# 06_POWER.net
KiCad netlist of a schematic drawn in Altium Designer
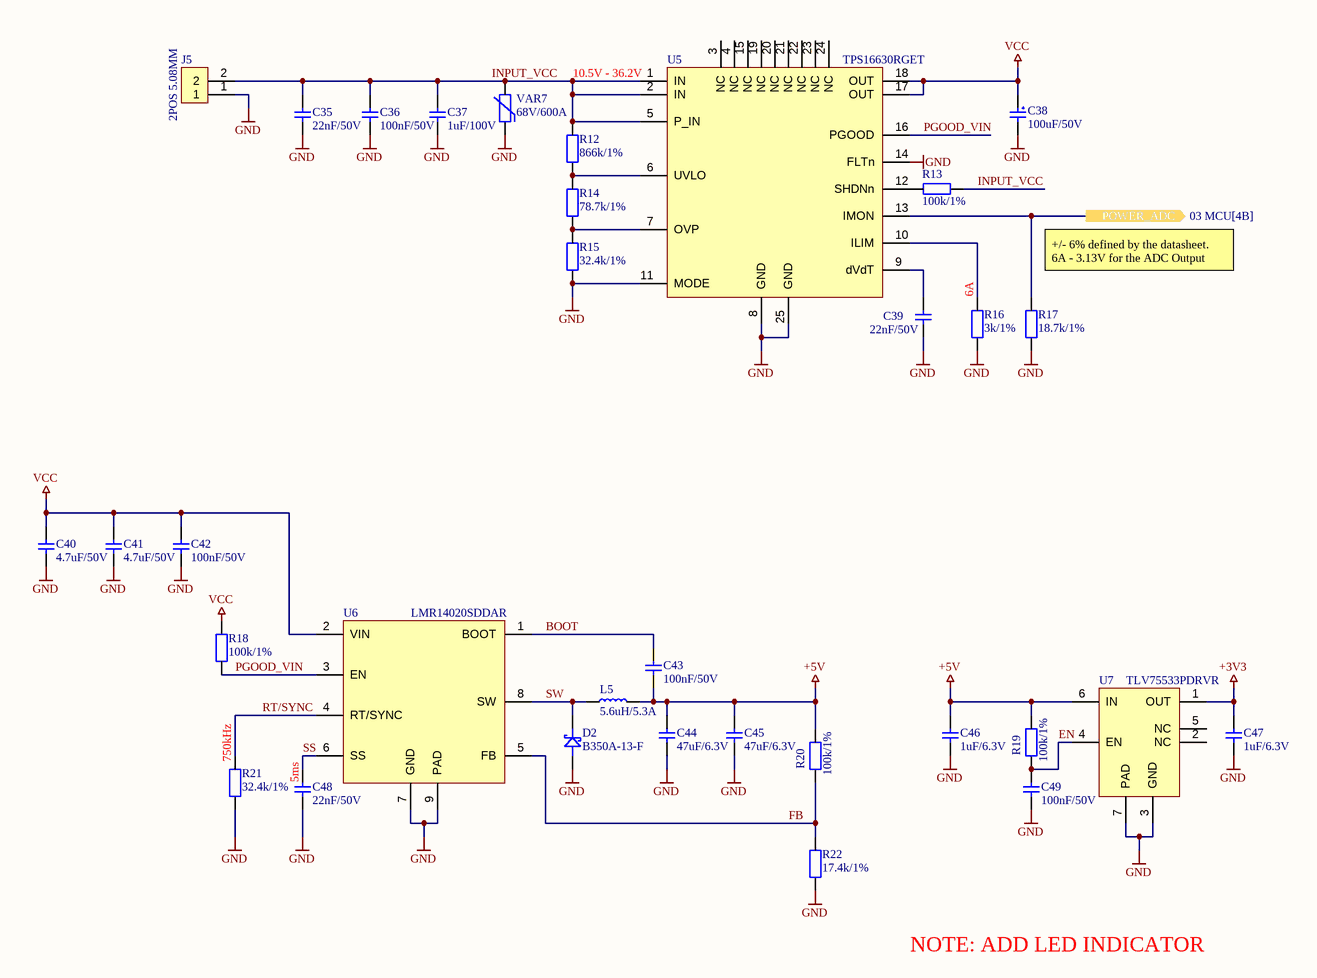
[diagram p0: 06 POWER.SchDoc]

(export (version "E")
  (design (tool "Eeschema 10.0.6"))
  (components
    (comp (ref "C35")
      (value "22nF/50V")
      (footprint "CAPC1005X06M-0402")
      (description "0.022 µF ±10% 50V Ceramic Capacitor X7R 0402 (1005 Metric)")
      (fields (field (name "MPN") "GRM155R71H223KA12D"))
      (libsource (lib "Symbol") (part "GRM155R71H223KA12D"))
    )
    (comp (ref "C36")
      (value "100nF/50V")
      (footprint "CAPC1005X06M-0402")
      (description "0.1 µF ±10% 50V Ceramic Capacitor X7R 0402 (1005 Metric)")
      (fields (field (name "MPN") "GRM155R71H104KE14D"))
      (libsource (lib "Symbol") (part "GRM155R71H104KE14D"))
    )
    (comp (ref "C37")
      (value "1uF/100V")
      (footprint "CAPC2012X14M")
      (description "1 µF ±10% 100V Ceramic Capacitor X7S 0805 (2012 Metric)")
      (fields (field (name "MPN") "GRM21BC72A105KE01L"))
      (libsource (lib "Symbol") (part "GRM21BC72A105KE01L"))
    )
    (comp (ref "C38")
      (value "100uF/50V")
      (footprint "A768KS107M1HLAE030")
      (description "100 µF 50 V Aluminum - Polymer Capacitors Radial, Can - SMD 30mOhm 2000 Hrs @ 125°C")
      (fields (field (name "MPN") "A768KS107M1HLAE030"))
      (libsource (lib "Symbol") (part "A768KS107M1HLAE030"))
    )
    (comp (ref "C39")
      (value "22nF/50V")
      (footprint "CAPC1005X06M-0402")
      (description "0.022 µF ±10% 50V Ceramic Capacitor X7R 0402 (1005 Metric)")
      (fields (field (name "MPN") "GRM155R71H223KA12D"))
      (libsource (lib "Symbol") (part "GRM155R71H223KA12D"))
    )
    (comp (ref "C40")
      (value "4.7uF/50V")
      (footprint "CAPC2012X14M")
      (description "4.7 µF ±10% 50V Ceramic Capacitor X5R 0805 (2012 Metric)")
      (fields (field (name "MPN") "GRM21BR61H475KE51L"))
      (libsource (lib "Symbol") (part "GRM21BR61H475KE51L"))
    )
    (comp (ref "C41")
      (value "4.7uF/50V")
      (footprint "CAPC2012X14M")
      (description "4.7 µF ±10% 50V Ceramic Capacitor X5R 0805 (2012 Metric)")
      (fields (field (name "MPN") "GRM21BR61H475KE51L"))
      (libsource (lib "Symbol") (part "GRM21BR61H475KE51L"))
    )
    (comp (ref "C42")
      (value "100nF/50V")
      (footprint "CAPC1005X06M-0402")
      (description "0.1 µF ±10% 50V Ceramic Capacitor X7R 0402 (1005 Metric)")
      (fields (field (name "MPN") "GRM155R71H104KE14D"))
      (libsource (lib "Symbol") (part "GRM155R71H104KE14D"))
    )
    (comp (ref "C43")
      (value "100nF/50V")
      (footprint "CAPC1005X06M-0402")
      (description "0.1 µF ±10% 50V Ceramic Capacitor X7R 0402 (1005 Metric)")
      (fields (field (name "MPN") "GRM155R71H104KE14D"))
      (libsource (lib "Symbol") (part "GRM155R71H104KE14D"))
    )
    (comp (ref "C44")
      (value "47uF/6.3V")
      (footprint "CAPC1608X10M-0603")
      (description "47 µF ±20% 6.3V Ceramic Capacitor X5R 0603 (1608 Metric)")
      (fields (field (name "MPN") "GRM188R60J476ME15D"))
      (libsource (lib "Symbol") (part "GRM188R60J476ME15D"))
    )
    (comp (ref "C45")
      (value "47uF/6.3V")
      (footprint "CAPC1608X10M-0603")
      (description "47 µF ±20% 6.3V Ceramic Capacitor X5R 0603 (1608 Metric)")
      (fields (field (name "MPN") "GRM188R60J476ME15D"))
      (libsource (lib "Symbol") (part "GRM188R60J476ME15D"))
    )
    (comp (ref "C46")
      (value "1uF/6.3V")
      (footprint "CAPC1005X06M-0402")
      (description "1 µF ±10% 6.3V Ceramic Capacitor X7R 0402 (1005 Metric)")
      (fields (field (name "MPN") "GRM155R70J105KA12J"))
      (libsource (lib "Symbol") (part "GRM155R70J105KA12J"))
    )
    (comp (ref "C47")
      (value "1uF/6.3V")
      (footprint "CAPC1005X06M-0402")
      (description "1 µF ±10% 6.3V Ceramic Capacitor X7R 0402 (1005 Metric)")
      (fields (field (name "MPN") "GRM155R70J105KA12J"))
      (libsource (lib "Symbol") (part "GRM155R70J105KA12J"))
    )
    (comp (ref "C48")
      (value "22nF/50V")
      (footprint "CAPC1005X06M-0402")
      (description "0.022 µF ±10% 50V Ceramic Capacitor X7R 0402 (1005 Metric)")
      (fields (field (name "MPN") "GRM155R71H223KA12D"))
      (libsource (lib "Symbol") (part "GRM155R71H223KA12D"))
    )
    (comp (ref "C49")
      (value "100nF/50V")
      (footprint "CAPC1005X06M-0402")
      (description "0.1 µF ±10% 50V Ceramic Capacitor X7R 0402 (1005 Metric)")
      (fields (field (name "MPN") "GRM155R71H104KE14D"))
      (libsource (lib "Symbol") (part "GRM155R71H104KE14D"))
    )
    (comp (ref "D2")
      (value "B350A-13-F")
      (footprint "SMA")
      (description "Diode 50 V 3A Surface Mount SMA")
      (libsource (lib "Symbol") (part "B350A-13-F"))
    )
    (comp (ref "J5")
      (value "2POS 5.08MM")
      (footprint "282837-2")
      (fields (field (name "MPN") "282834-3"))
      (libsource (lib "Symbol") (part "282837-2"))
    )
    (comp (ref "L5")
      (value "5.6uH/5.3A")
      (footprint "IHLP2525CZER5R6M8A")
      (description "5.6 µH Shielded Molded Inductor 5.3 A 45.6mOhm Max Nonstandard")
      (fields (field (name "MPN") "IHLP2525CZER5R6M8A"))
      (libsource (lib "Symbol") (part "IHLP2525CZER5R6M8A"))
    )
    (comp (ref "R12")
      (value "866k/1%")
      (footprint "RESC1005X04M-0402")
      (description "866 kOhms ±1% 0.063W, 1/16W Chip Resistor 0402 (1005 Metric) Moisture Resistant Thick Film")
      (fields (field (name "MPN") "RC0402FR-07866KL"))
      (libsource (lib "Symbol") (part "RC0402FR-07866KL"))
    )
    (comp (ref "R13")
      (value "100k/1%")
      (footprint "RESC1005X04M-0402")
      (description "100 kOhms ±1% 0.063W, 1/16W Chip Resistor 0402 (1005 Metric) Moisture Resistant Thick Film")
      (fields (field (name "MPN") "RC0402FR-07100KL"))
      (libsource (lib "Symbol") (part "RC0402FR-07100KL"))
    )
    (comp (ref "R14")
      (value "78.7k/1%")
      (footprint "RESC1005X04M-0402")
      (description "78.7 kOhms ±1% 0.063W, 1/16W Chip Resistor 0402 (1005 Metric) Moisture Resistant Thick Film")
      (fields (field (name "MPN") "RC0402FR-0778K7L"))
      (libsource (lib "Symbol") (part "RC0402FR-0778K7L"))
    )
    (comp (ref "R15")
      (value "32.4k/1%")
      (footprint "RESC1005X04M-0402")
      (description "32.4 kOhms ±1% 0.063W, 1/16W Chip Resistor 0402 (1005 Metric) Moisture Resistant Thick Film")
      (fields (field (name "MPN") "RC0402FR-0718K7L"))
      (libsource (lib "Symbol") (part "RC0402FR-0732K4L"))
    )
    (comp (ref "R16")
      (value "3k/1%")
      (footprint "RESC1005X04M-0402")
      (description "3 kOhms ±1% 0.063W, 1/16W Chip Resistor 0402 (1005 Metric) Moisture Resistant Thick Film")
      (fields (field (name "MPN") "RC0402FR-073KL"))
      (libsource (lib "Symbol") (part "RC0402FR-073KL"))
    )
    (comp (ref "R17")
      (value "18.7k/1%")
      (footprint "RESC1005X04M-0402")
      (description "18.7 kOhms ±1% 0.063W, 1/16W Chip Resistor 0402 (1005 Metric) Moisture Resistant Thick Film")
      (fields (field (name "MPN") "RC0402FR-0718K7L"))
      (libsource (lib "Symbol") (part "RC0402FR-0718K7L"))
    )
    (comp (ref "R18")
      (value "100k/1%")
      (footprint "RESC1005X04M-0402")
      (description "100 kOhms ±1% 0.063W, 1/16W Chip Resistor 0402 (1005 Metric) Moisture Resistant Thick Film")
      (fields (field (name "MPN") "RC0402FR-07100KL"))
      (libsource (lib "Symbol") (part "RC0402FR-07100KL"))
    )
    (comp (ref "R19")
      (value "100k/1%")
      (footprint "RESC1005X04M-0402")
      (description "100 kOhms ±1% 0.063W, 1/16W Chip Resistor 0402 (1005 Metric) Moisture Resistant Thick Film")
      (fields (field (name "MPN") "RC0402FR-07100KL"))
      (libsource (lib "Symbol") (part "RC0402FR-07100KL"))
    )
    (comp (ref "R20")
      (value "100k/1%")
      (footprint "RESC1005X04M-0402")
      (description "100 kOhms ±1% 0.063W, 1/16W Chip Resistor 0402 (1005 Metric) Moisture Resistant Thick Film")
      (fields (field (name "MPN") "RC0402FR-07100KL"))
      (libsource (lib "Symbol") (part "RC0402FR-07100KL"))
    )
    (comp (ref "R21")
      (value "32.4k/1%")
      (footprint "RESC1005X04M-0402")
      (description "32.4 kOhms ±1% 0.063W, 1/16W Chip Resistor 0402 (1005 Metric) Moisture Resistant Thick Film")
      (fields (field (name "MPN") "RC0402FR-0718K7L"))
      (libsource (lib "Symbol") (part "RC0402FR-0732K4L"))
    )
    (comp (ref "R22")
      (value "17.4k/1%")
      (footprint "RESC1005X04M-0402")
      (description "17.4 kOhms ±1% 0.063W, 1/16W Chip Resistor 0402 (1005 Metric) Moisture Resistant Thick Film")
      (fields (field (name "MPN") "RC0402FR-0717K4L"))
      (libsource (lib "Symbol") (part "RC0402FR-0717K4L"))
    )
    (comp (ref "U5")
      (value "TPS16630RGET")
      (footprint "PQFN50P400X400X100_HS-25N")
      (description "Electronic Fuse Regulator 6A 24-VQFN (4x4)")
      (libsource (lib "Symbol") (part "TPS16630RGET"))
    )
    (comp (ref "U6")
      (value "LMR14020SDDAR")
      (footprint "SOIC127P600X170_HS-9N")
      (libsource (lib "Symbol") (part "LMR14020SDDAR"))
    )
    (comp (ref "U7")
      (value "TLV75533PDRVR")
      (footprint "SON65P200X80_HS-7N")
      (description "Linear Voltage Regulator IC Positive Fixed 1 Output 500mA 6-WSON (2x2)")
      (libsource (lib "Symbol") (part "TLV75533PDRVR"))
    )
    (comp (ref "VAR7")
      (value "68V/600A")
      (footprint "VARA4732X16N")
      (description "68 V 600 A Varistor 1 Circuit Surface Mount, MLCV 1812 (4532 Metric)")
      (fields (field (name "MPN") "ZV40K1812601NIR1"))
      (libsource (lib "Symbol") (part "ZV40K1812601NIR1"))
    )
  )
  (nets
    (net (code "1") (name "+3V3") (class "Default")
      (node (ref "C47") (pin "2") (pinfunction "2_2") (pintype "passive"))
      (node (ref "U7") (pin "1") (pinfunction "OUT_1") (pintype "passive"))
    )
    (net (code "2") (name "+5V") (class "Default")
      (node (ref "C43") (pin "1") (pinfunction "1_1") (pintype "passive"))
      (node (ref "C44") (pin "2") (pinfunction "2_2") (pintype "passive"))
      (node (ref "C45") (pin "2") (pinfunction "2_2") (pintype "passive"))
      (node (ref "C46") (pin "2") (pinfunction "2_2") (pintype "passive"))
      (node (ref "L5") (pin "2") (pinfunction "2_2") (pintype "passive"))
      (node (ref "R19") (pin "2") (pinfunction "2_2") (pintype "passive"))
      (node (ref "R20") (pin "2") (pinfunction "2_2") (pintype "passive"))
      (node (ref "U7") (pin "6") (pinfunction "IN_6") (pintype "passive"))
    )
    (net (code "3") (name "/BOOT") (class "Default")
      (node (ref "C43") (pin "2") (pinfunction "2_2") (pintype "passive"))
      (node (ref "U6") (pin "1") (pinfunction "BOOT_1") (pintype "passive"))
    )
    (net (code "4") (name "/EN") (class "Default")
      (node (ref "C49") (pin "2") (pinfunction "2_2") (pintype "passive"))
      (node (ref "R19") (pin "1") (pinfunction "1_1") (pintype "passive"))
      (node (ref "U7") (pin "4") (pinfunction "EN_4") (pintype "passive"))
    )
    (net (code "5") (name "/FB") (class "Default")
      (node (ref "R20") (pin "1") (pinfunction "1_1") (pintype "passive"))
      (node (ref "R22") (pin "2") (pinfunction "2_2") (pintype "passive"))
      (node (ref "U6") (pin "5") (pinfunction "FB_5") (pintype "passive"))
    )
    (net (code "6") (name "/INPUT_VCC") (class "Default")
      (node (ref "C35") (pin "2") (pinfunction "2_2") (pintype "passive"))
      (node (ref "C36") (pin "2") (pinfunction "2_2") (pintype "passive"))
      (node (ref "C37") (pin "2") (pinfunction "2_2") (pintype "passive"))
      (node (ref "J5") (pin "2") (pinfunction "2_2") (pintype "passive"))
      (node (ref "R12") (pin "2") (pinfunction "2_2") (pintype "passive"))
      (node (ref "R13") (pin "1") (pinfunction "1_1") (pintype "passive"))
      (node (ref "U5") (pin "1") (pinfunction "IN_1") (pintype "power_in"))
      (node (ref "U5") (pin "2") (pinfunction "IN_2") (pintype "power_in"))
      (node (ref "U5") (pin "5") (pinfunction "P_IN_5") (pintype "passive"))
      (node (ref "VAR7") (pin "2") (pinfunction "2_2") (pintype "passive"))
    )
    (net (code "7") (name "/PGOOD_VIN") (class "Default")
      (node (ref "R18") (pin "2") (pinfunction "2_2") (pintype "passive"))
      (node (ref "U5") (pin "16") (pinfunction "PGOOD_16") (pintype "passive"))
      (node (ref "U6") (pin "3") (pinfunction "EN_3") (pintype "passive"))
    )
    (net (code "8") (name "/POWER_ADC") (class "Default")
      (node (ref "R17") (pin "2") (pinfunction "2_2") (pintype "passive"))
      (node (ref "U5") (pin "13") (pinfunction "IMON_13") (pintype "passive"))
    )
    (net (code "9") (name "/RT{slash}SYNC") (class "Default")
      (node (ref "R21") (pin "2") (pinfunction "2_2") (pintype "passive"))
      (node (ref "U6") (pin "4") (pinfunction "RT/SYNC_4") (pintype "passive"))
    )
    (net (code "10") (name "/SS") (class "Default")
      (node (ref "C48") (pin "1") (pinfunction "1_1") (pintype "passive"))
      (node (ref "U6") (pin "6") (pinfunction "SS_6") (pintype "passive"))
    )
    (net (code "11") (name "/SW") (class "Default")
      (node (ref "D2") (pin "1") (pinfunction "1_1") (pintype "passive"))
      (node (ref "L5") (pin "1") (pinfunction "1_1") (pintype "passive"))
      (node (ref "U6") (pin "8") (pinfunction "SW_8") (pintype "passive"))
    )
    (net (code "12") (name "GND") (class "Default")
      (node (ref "C35") (pin "1") (pinfunction "1_1") (pintype "passive"))
      (node (ref "C36") (pin "1") (pinfunction "1_1") (pintype "passive"))
      (node (ref "C37") (pin "1") (pinfunction "1_1") (pintype "passive"))
      (node (ref "C38") (pin "2") (pinfunction "2_2") (pintype "passive"))
      (node (ref "C39") (pin "1") (pinfunction "1_1") (pintype "passive"))
      (node (ref "C40") (pin "1") (pinfunction "1_1") (pintype "passive"))
      (node (ref "C41") (pin "1") (pinfunction "1_1") (pintype "passive"))
      (node (ref "C42") (pin "1") (pinfunction "1_1") (pintype "passive"))
      (node (ref "C44") (pin "1") (pinfunction "1_1") (pintype "passive"))
      (node (ref "C45") (pin "1") (pinfunction "1_1") (pintype "passive"))
      (node (ref "C46") (pin "1") (pinfunction "1_1") (pintype "passive"))
      (node (ref "C47") (pin "1") (pinfunction "1_1") (pintype "passive"))
      (node (ref "C48") (pin "2") (pinfunction "2_2") (pintype "passive"))
      (node (ref "C49") (pin "1") (pinfunction "1_1") (pintype "passive"))
      (node (ref "D2") (pin "2") (pinfunction "2_2") (pintype "passive"))
      (node (ref "J5") (pin "1") (pinfunction "1_1") (pintype "passive"))
      (node (ref "R15") (pin "1") (pinfunction "1_1") (pintype "passive"))
      (node (ref "R16") (pin "1") (pinfunction "1_1") (pintype "passive"))
      (node (ref "R17") (pin "1") (pinfunction "1_1") (pintype "passive"))
      (node (ref "R21") (pin "1") (pinfunction "1_1") (pintype "passive"))
      (node (ref "R22") (pin "1") (pinfunction "1_1") (pintype "passive"))
      (node (ref "U5") (pin "11") (pinfunction "MODE_11") (pintype "passive"))
      (node (ref "U5") (pin "14") (pinfunction "FLTn_14") (pintype "passive"))
      (node (ref "U5") (pin "25") (pinfunction "GND_25") (pintype "passive"))
      (node (ref "U5") (pin "8") (pinfunction "GND_8") (pintype "power_in"))
      (node (ref "U6") (pin "7") (pinfunction "GND_7") (pintype "passive"))
      (node (ref "U6") (pin "9") (pinfunction "PAD_9") (pintype "passive"))
      (node (ref "U7") (pin "3") (pinfunction "GND_3") (pintype "passive"))
      (node (ref "U7") (pin "7") (pinfunction "PAD_7") (pintype "passive"))
      (node (ref "VAR7") (pin "1") (pinfunction "1_1") (pintype "passive"))
    )
    (net (code "13") (name "Net-(U5-ILIM)") (class "Default")
      (node (ref "R16") (pin "2") (pinfunction "2_2") (pintype "passive"))
      (node (ref "U5") (pin "10") (pinfunction "ILIM_10") (pintype "passive"))
    )
    (net (code "14") (name "Net-(U5-OVP)") (class "Default")
      (node (ref "R14") (pin "1") (pinfunction "1_1") (pintype "passive"))
      (node (ref "R15") (pin "2") (pinfunction "2_2") (pintype "passive"))
      (node (ref "U5") (pin "7") (pinfunction "OVP_7") (pintype "passive"))
    )
    (net (code "15") (name "Net-(U5-SHDNn)") (class "Default")
      (node (ref "R13") (pin "2") (pinfunction "2_2") (pintype "passive"))
      (node (ref "U5") (pin "12") (pinfunction "SHDNn_12") (pintype "passive"))
    )
    (net (code "16") (name "Net-(U5-UVLO)") (class "Default")
      (node (ref "R12") (pin "1") (pinfunction "1_1") (pintype "passive"))
      (node (ref "R14") (pin "2") (pinfunction "2_2") (pintype "passive"))
      (node (ref "U5") (pin "6") (pinfunction "UVLO_6") (pintype "passive"))
    )
    (net (code "17") (name "Net-(U5-dVdT)") (class "Default")
      (node (ref "C39") (pin "2") (pinfunction "2_2") (pintype "passive"))
      (node (ref "U5") (pin "9") (pinfunction "dVdT_9") (pintype "passive"))
    )
    (net (code "18") (name "VCC") (class "Default")
      (node (ref "C38") (pin "1") (pinfunction "1_1") (pintype "passive"))
      (node (ref "C40") (pin "2") (pinfunction "2_2") (pintype "passive"))
      (node (ref "C41") (pin "2") (pinfunction "2_2") (pintype "passive"))
      (node (ref "C42") (pin "2") (pinfunction "2_2") (pintype "passive"))
      (node (ref "R18") (pin "1") (pinfunction "1_1") (pintype "passive"))
      (node (ref "U5") (pin "17") (pinfunction "OUT_17") (pintype "power_in"))
      (node (ref "U5") (pin "18") (pinfunction "OUT_18") (pintype "power_in"))
      (node (ref "U6") (pin "2") (pinfunction "VIN_2") (pintype "passive"))
    )
    (net (code "19") (name "unconnected-(U5-NC-Pad3)") (class "Default")
      (node (ref "U5") (pin "3") (pinfunction "NC_3") (pintype "passive"))
    )
    (net (code "20") (name "unconnected-(U5-NC-Pad4)") (class "Default")
      (node (ref "U5") (pin "4") (pinfunction "NC_4") (pintype "passive"))
    )
    (net (code "21") (name "unconnected-(U5-NC-Pad15)") (class "Default")
      (node (ref "U5") (pin "15") (pinfunction "NC_15") (pintype "passive"))
    )
    (net (code "22") (name "unconnected-(U5-NC-Pad19)") (class "Default")
      (node (ref "U5") (pin "19") (pinfunction "NC_19") (pintype "passive"))
    )
    (net (code "23") (name "unconnected-(U5-NC-Pad20)") (class "Default")
      (node (ref "U5") (pin "20") (pinfunction "NC_20") (pintype "passive"))
    )
    (net (code "24") (name "unconnected-(U5-NC-Pad21)") (class "Default")
      (node (ref "U5") (pin "21") (pinfunction "NC_21") (pintype "passive"))
    )
    (net (code "25") (name "unconnected-(U5-NC-Pad22)") (class "Default")
      (node (ref "U5") (pin "22") (pinfunction "NC_22") (pintype "passive"))
    )
    (net (code "26") (name "unconnected-(U5-NC-Pad23)") (class "Default")
      (node (ref "U5") (pin "23") (pinfunction "NC_23") (pintype "passive"))
    )
    (net (code "27") (name "unconnected-(U5-NC-Pad24)") (class "Default")
      (node (ref "U5") (pin "24") (pinfunction "NC_24") (pintype "passive"))
    )
    (net (code "28") (name "unconnected-(U7-NC-Pad2)") (class "Default")
      (node (ref "U7") (pin "2") (pinfunction "NC_2") (pintype "passive"))
    )
    (net (code "29") (name "unconnected-(U7-NC-Pad5)") (class "Default")
      (node (ref "U7") (pin "5") (pinfunction "NC_5") (pintype "passive"))
    )
  )
)
